# smartFridgeController.net
KiCad netlist of a schematic drawn in EAGLE
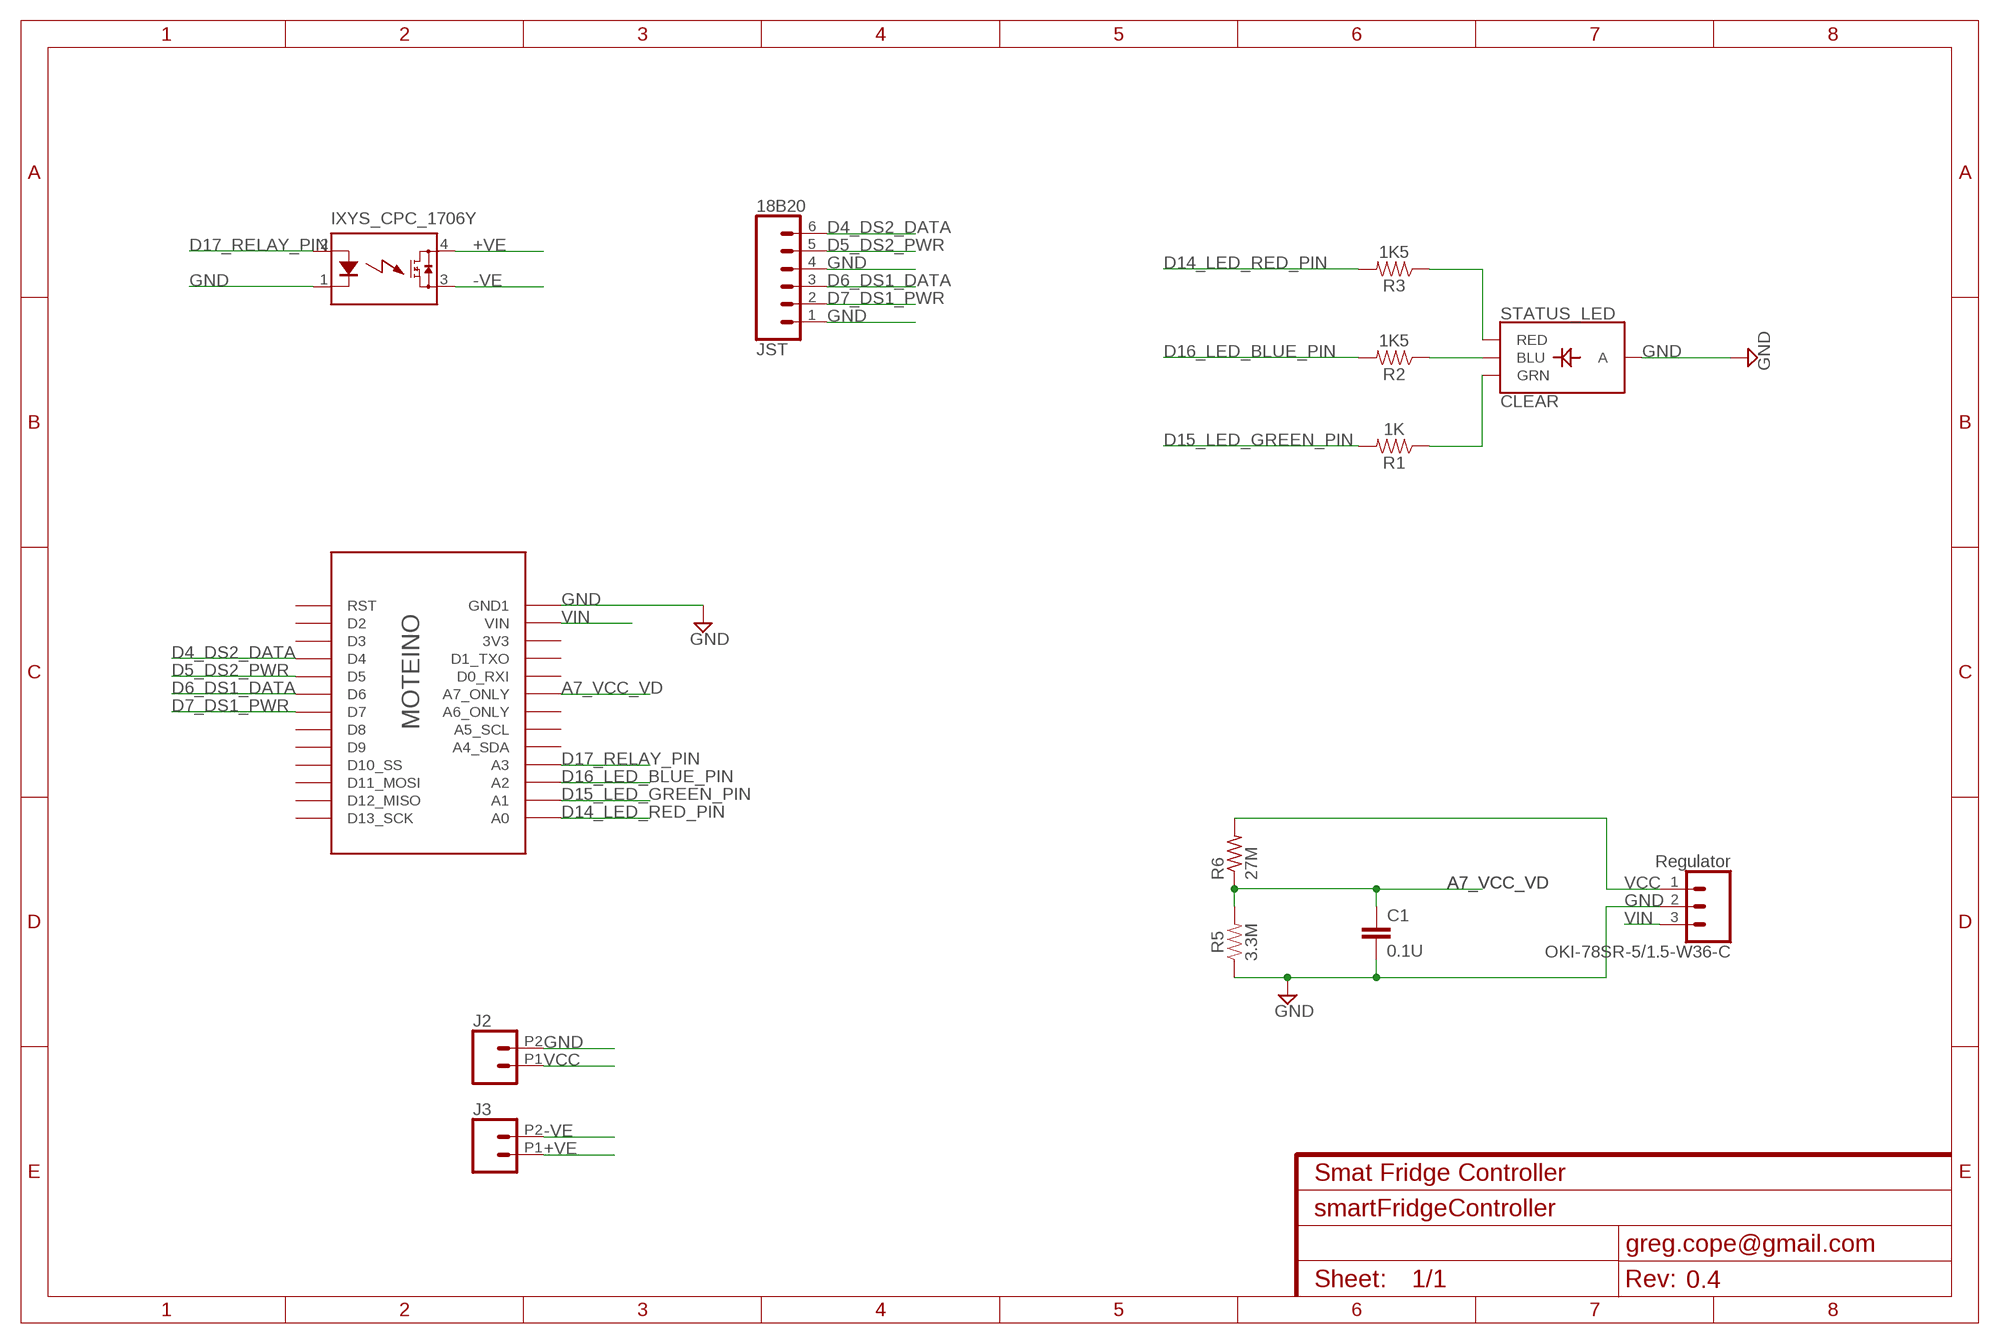
[diagram p0: schematic, sheet 1]

(export (version "E")
  (design (tool "Eeschema 10.0.6"))
  (components
    (comp (ref "18B20")
      (value "JST")
      (footprint "eagle-import:1X06")
      (libsource (lib "eagle-import") (part "CONN_06SILK_FEMALE_PTH"))
    )
    (comp (ref "C1")
      (value "0.1U")
      (footprint "eagle-import:CAP-PTH-SMALL-KIT")
      (libsource (lib "eagle-import") (part "0.1UF-KIT-EZ-50V-20%"))
    )
    (comp (ref "IXYS_CPC_1706Y")
      (value "AQZ102D")
      (footprint "eagle-import:AQZ-SIL04")
      (fields (field (name "MF") "AROMAT/ MATSUSHITA"))
      (libsource (lib "eagle-import") (part "AQZ10D2"))
    )
    (comp (ref "J2")
      (value "CONN_022.54MM_SCREWTERM")
      (footprint "eagle-import:1X02_2.54_SCREWTERM")
      (libsource (lib "eagle-import") (part "CONN_022.54MM_SCREWTERM"))
    )
    (comp (ref "J3")
      (value "CONN_022.54MM_SCREWTERM")
      (footprint "eagle-import:1X02_2.54_SCREWTERM")
      (libsource (lib "eagle-import") (part "CONN_022.54MM_SCREWTERM"))
    )
    (comp (ref "OKI-78SR-5/1.5-W36-C")
      (value "Regulator")
      (footprint "eagle-import:1X03")
      (libsource (lib "eagle-import") (part "CONN_03"))
    )
    (comp (ref "R1")
      (value "1K")
      (footprint "eagle-import:AXIAL-0.3")
      (libsource (lib "eagle-import") (part "1KOHM-HORIZ-1/4W-1%"))
    )
    (comp (ref "R2")
      (value "1K5")
      (footprint "eagle-import:AXIAL-0.3")
      (libsource (lib "eagle-import") (part "1KOHM-HORIZ-1/4W-1%"))
    )
    (comp (ref "R3")
      (value "1K5")
      (footprint "eagle-import:AXIAL-0.3")
      (libsource (lib "eagle-import") (part "1KOHM-HORIZ-1/4W-1%"))
    )
    (comp (ref "R5")
      (value "3.3M")
      (footprint "eagle-import:AXIAL-0.3")
      (libsource (lib "eagle-import") (part "1KOHM-HORIZ-1/4W-1%"))
    )
    (comp (ref "R6")
      (value "27M")
      (footprint "eagle-import:0309_12")
      (libsource (lib "eagle-import") (part "R-US_0309/12"))
    )
    (comp (ref "STATUS_LED")
      (value "CLEAR")
      (footprint "eagle-import:LED-RGB-THRU")
      (libsource (lib "eagle-import") (part "LED-RGB-CACLEAR"))
    )
    (comp (ref "U$2")
      (value "MOTEINO_SIMPLE")
      (footprint "eagle-import:MOTEINO_SIMPLE")
      (libsource (lib "eagle-import") (part "MOTEINO_SIMPLE"))
    )
  )
  (nets
    (net (code "1") (name "/+VE") (class "Default")
      (node (ref "IXYS_CPC_1706Y") (pin "4") (pinfunction "DS1_4") (pintype "passive"))
      (node (ref "J3") (pin "P1") (pinfunction "1_P1") (pintype "passive"))
    )
    (net (code "2") (name "/-VE") (class "Default")
      (node (ref "IXYS_CPC_1706Y") (pin "3") (pinfunction "DS2_3") (pintype "passive"))
      (node (ref "J3") (pin "P2") (pinfunction "2_P2") (pintype "passive"))
    )
    (net (code "3") (name "/A7_VCC_VD") (class "Default")
      (node (ref "C1") (pin "1") (pinfunction "1_1") (pintype "passive"))
      (node (ref "R5") (pin "P$2") (pinfunction "2_P$2") (pintype "passive"))
      (node (ref "R6") (pin "1") (pinfunction "1_1") (pintype "passive"))
      (node (ref "U$2") (pin "A7_ONLY") (pinfunction "A7_ONLY_A7_ONLY") (pintype "bidirectional"))
    )
    (net (code "4") (name "/D4_DS2_DATA") (class "Default")
      (node (ref "18B20") (pin "6") (pinfunction "6_6") (pintype "passive"))
      (node (ref "U$2") (pin "D4") (pinfunction "D4_D4") (pintype "bidirectional"))
    )
    (net (code "5") (name "/D5_DS2_PWR") (class "Default")
      (node (ref "18B20") (pin "5") (pinfunction "5_5") (pintype "passive"))
      (node (ref "U$2") (pin "D5") (pinfunction "D5_D5") (pintype "bidirectional"))
    )
    (net (code "6") (name "/D6_DS1_DATA") (class "Default")
      (node (ref "18B20") (pin "3") (pinfunction "3_3") (pintype "passive"))
      (node (ref "U$2") (pin "D6") (pinfunction "D6_D6") (pintype "bidirectional"))
    )
    (net (code "7") (name "/D7_DS1_PWR") (class "Default")
      (node (ref "18B20") (pin "2") (pinfunction "2_2") (pintype "passive"))
      (node (ref "U$2") (pin "D7") (pinfunction "D7_D7") (pintype "bidirectional"))
    )
    (net (code "8") (name "/D14_LED_RED_PIN") (class "Default")
      (node (ref "R3") (pin "P$2") (pinfunction "2_P$2") (pintype "passive"))
      (node (ref "U$2") (pin "A0") (pinfunction "A0_A0") (pintype "bidirectional"))
    )
    (net (code "9") (name "/D15_LED_GREEN_PIN") (class "Default")
      (node (ref "R1") (pin "P$2") (pinfunction "2_P$2") (pintype "passive"))
      (node (ref "U$2") (pin "A1") (pinfunction "A1_A1") (pintype "bidirectional"))
    )
    (net (code "10") (name "/D16_LED_BLUE_PIN") (class "Default")
      (node (ref "R2") (pin "P$2") (pinfunction "2_P$2") (pintype "passive"))
      (node (ref "U$2") (pin "A2") (pinfunction "A2_A2") (pintype "bidirectional"))
    )
    (net (code "11") (name "/D17_RELAY_PIN") (class "Default")
      (node (ref "IXYS_CPC_1706Y") (pin "2") (pinfunction "A_2") (pintype "passive"))
      (node (ref "U$2") (pin "A3") (pinfunction "A3_A3") (pintype "bidirectional"))
    )
    (net (code "12") (name "/VCC") (class "Default")
      (node (ref "J2") (pin "P1") (pinfunction "1_P1") (pintype "passive"))
      (node (ref "OKI-78SR-5/1.5-W36-C") (pin "1") (pinfunction "1_1") (pintype "passive"))
      (node (ref "R6") (pin "2") (pinfunction "2_2") (pintype "passive"))
    )
    (net (code "13") (name "/VIN") (class "Default")
      (node (ref "OKI-78SR-5/1.5-W36-C") (pin "3") (pinfunction "3_3") (pintype "passive"))
      (node (ref "U$2") (pin "VIN") (pinfunction "VIN_VIN") (pintype "bidirectional"))
    )
    (net (code "14") (name "GND") (class "Default")
      (node (ref "18B20") (pin "1") (pinfunction "1_1") (pintype "passive"))
      (node (ref "18B20") (pin "4") (pinfunction "4_4") (pintype "passive"))
      (node (ref "C1") (pin "2") (pinfunction "2_2") (pintype "passive"))
      (node (ref "IXYS_CPC_1706Y") (pin "1") (pinfunction "K_1") (pintype "passive"))
      (node (ref "J2") (pin "P2") (pinfunction "2_P2") (pintype "passive"))
      (node (ref "OKI-78SR-5/1.5-W36-C") (pin "2") (pinfunction "2_2") (pintype "passive"))
      (node (ref "R5") (pin "P$1") (pinfunction "1_P$1") (pintype "passive"))
      (node (ref "STATUS_LED") (pin "2") (pinfunction "A_2") (pintype "bidirectional"))
      (node (ref "U$2") (pin "GND1") (pinfunction "GND1_GND1") (pintype "bidirectional"))
    )
    (net (code "15") (name "Net-(R1-1)") (class "Default")
      (node (ref "R1") (pin "P$1") (pinfunction "1_P$1") (pintype "passive"))
      (node (ref "STATUS_LED") (pin "3") (pinfunction "GRN_3") (pintype "bidirectional"))
    )
    (net (code "16") (name "Net-(R2-1)") (class "Default")
      (node (ref "R2") (pin "P$1") (pinfunction "1_P$1") (pintype "passive"))
      (node (ref "STATUS_LED") (pin "4") (pinfunction "BLU_4") (pintype "bidirectional"))
    )
    (net (code "17") (name "Net-(R3-1)") (class "Default")
      (node (ref "R3") (pin "P$1") (pinfunction "1_P$1") (pintype "passive"))
      (node (ref "STATUS_LED") (pin "1") (pinfunction "RED_1") (pintype "bidirectional"))
    )
    (net (code "18") (name "unconnected-(U$2-Pad3V3)") (class "Default")
      (node (ref "U$2") (pin "3V3") (pinfunction "3V3_3V3") (pintype "bidirectional"))
    )
    (net (code "19") (name "unconnected-(U$2-PadA4_SDA)") (class "Default")
      (node (ref "U$2") (pin "A4_SDA") (pinfunction "A4_SDA_A4_SDA") (pintype "bidirectional"))
    )
    (net (code "20") (name "unconnected-(U$2-PadA5_SCL)") (class "Default")
      (node (ref "U$2") (pin "A5_SCL") (pinfunction "A5_SCL_A5_SCL") (pintype "bidirectional"))
    )
    (net (code "21") (name "unconnected-(U$2-PadA6_ONLY)") (class "Default")
      (node (ref "U$2") (pin "A6_ONLY") (pinfunction "A6_ONLY_A6_ONLY") (pintype "bidirectional"))
    )
    (net (code "22") (name "unconnected-(U$2-PadD0_RXI)") (class "Default")
      (node (ref "U$2") (pin "D0_RXI") (pinfunction "D0_RXI_D0_RXI") (pintype "bidirectional"))
    )
    (net (code "23") (name "unconnected-(U$2-PadD1_TXO)") (class "Default")
      (node (ref "U$2") (pin "D1_TXO") (pinfunction "D1_TXO_D1_TXO") (pintype "bidirectional"))
    )
    (net (code "24") (name "unconnected-(U$2-PadD2)") (class "Default")
      (node (ref "U$2") (pin "D2") (pinfunction "D2_D2") (pintype "bidirectional"))
    )
    (net (code "25") (name "unconnected-(U$2-PadD3)") (class "Default")
      (node (ref "U$2") (pin "D3") (pinfunction "D3_D3") (pintype "bidirectional"))
    )
    (net (code "26") (name "unconnected-(U$2-PadD8)") (class "Default")
      (node (ref "U$2") (pin "D8") (pinfunction "D8_D8") (pintype "bidirectional"))
    )
    (net (code "27") (name "unconnected-(U$2-PadD9)") (class "Default")
      (node (ref "U$2") (pin "D9") (pinfunction "D9_D9") (pintype "bidirectional"))
    )
    (net (code "28") (name "unconnected-(U$2-PadD10_SS)") (class "Default")
      (node (ref "U$2") (pin "D10_SS") (pinfunction "D10_SS_D10_SS") (pintype "bidirectional"))
    )
    (net (code "29") (name "unconnected-(U$2-PadD11_MOSI)") (class "Default")
      (node (ref "U$2") (pin "D11_MOSI") (pinfunction "D11_MOSI_D11_MOSI") (pintype "bidirectional"))
    )
    (net (code "30") (name "unconnected-(U$2-PadD12_MISO)") (class "Default")
      (node (ref "U$2") (pin "D12_MISO") (pinfunction "D12_MISO_D12_MISO") (pintype "bidirectional"))
    )
    (net (code "31") (name "unconnected-(U$2-PadD13_SCK)") (class "Default")
      (node (ref "U$2") (pin "D13_SCK") (pinfunction "D13_SCK_D13_SCK") (pintype "bidirectional"))
    )
    (net (code "32") (name "unconnected-(U$2-PadRST)") (class "Default")
      (node (ref "U$2") (pin "RST") (pinfunction "RST_RST") (pintype "bidirectional"))
    )
  )
)
